# JACK_DUAL_M2_v3.net
KiCad netlist of a schematic drawn in EAGLE
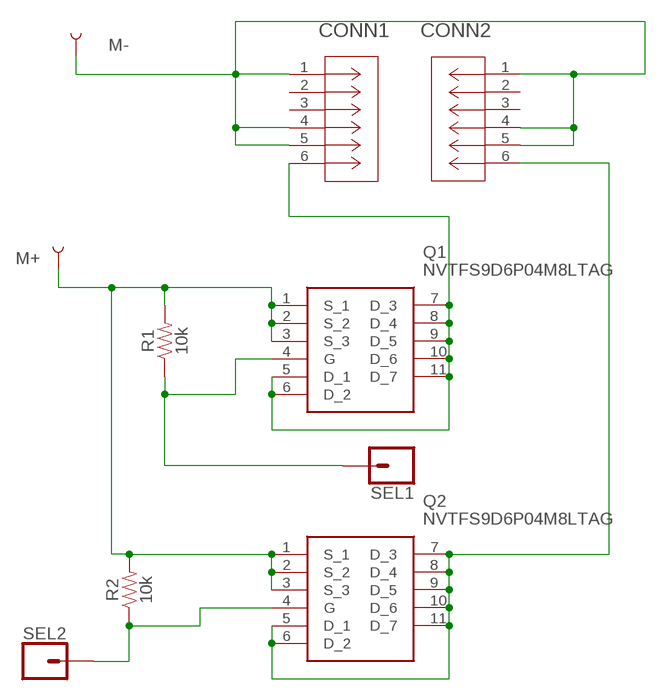
[diagram p0: schematic, sheet 1]

(export (version "E")
  (design (tool "Eeschema 10.0.6"))
  (components
    (comp (ref "CONN1")
      (value "ACJS-MHDR")
      (footprint "eagle-import:CONN_MHDR_AMP")
      (fields (field (name "COPYRIGHT") "Copyright (C) 2018 Accelerated Designs. All rights reserved"))
      (libsource (lib "eagle-import") (part "ACJS-MHDR"))
    )
    (comp (ref "CONN2")
      (value "ACJS-MHDR")
      (footprint "eagle-import:CONN_MHDR_AMP")
      (fields (field (name "COPYRIGHT") "Copyright (C) 2018 Accelerated Designs. All rights reserved"))
      (libsource (lib "eagle-import") (part "ACJS-MHDR"))
    )
    (comp (ref "M+")
      (value "TEST-POINT3")
      (footprint "eagle-import:PAD.03X.03")
      (libsource (lib "eagle-import") (part "TEST-POINT3"))
    )
    (comp (ref "M-")
      (value "TEST-POINT3")
      (footprint "eagle-import:PAD.03X.03")
      (libsource (lib "eagle-import") (part "TEST-POINT3"))
    )
    (comp (ref "Q1")
      (value "NVTFS9D6P04M8LTAG")
      (footprint "eagle-import:NVTFS5124PLTWG")
      (fields (field (name "MOUSER_PART_NUMBER") "863-NVTFS9D6P04M8LTG"))
      (libsource (lib "eagle-import") (part "NVTFS9D6P04M8LTAG"))
    )
    (comp (ref "Q2")
      (value "NVTFS9D6P04M8LTAG")
      (footprint "eagle-import:NVTFS5124PLTWG")
      (fields (field (name "MOUSER_PART_NUMBER") "863-NVTFS9D6P04M8LTG"))
      (libsource (lib "eagle-import") (part "NVTFS9D6P04M8LTAG"))
    )
    (comp (ref "R1")
      (value "10k")
      (footprint "eagle-import:0805")
      (libsource (lib "eagle-import") (part "RESISTOR0805"))
    )
    (comp (ref "R2")
      (value "10k")
      (footprint "eagle-import:0805")
      (libsource (lib "eagle-import") (part "RESISTOR0805"))
    )
    (comp (ref "SEL1")
      (value "CONN_01")
      (footprint "eagle-import:1X01")
      (libsource (lib "eagle-import") (part "CONN_01"))
    )
    (comp (ref "SEL2")
      (value "CONN_01")
      (footprint "eagle-import:1X01")
      (libsource (lib "eagle-import") (part "CONN_01"))
    )
  )
  (nets
    (net (code "1") (name "Net-(M+-1)") (class "Default")
      (node (ref "M+") (pin "P$1") (pinfunction "1_P$1") (pintype "bidirectional"))
      (node (ref "Q1") (pin "1") (pinfunction "S_1_1") (pintype "bidirectional"))
      (node (ref "Q1") (pin "2") (pinfunction "S_2_2") (pintype "bidirectional"))
      (node (ref "Q1") (pin "3") (pinfunction "S_3_3") (pintype "bidirectional"))
      (node (ref "Q2") (pin "1") (pinfunction "S_1_1") (pintype "bidirectional"))
      (node (ref "Q2") (pin "2") (pinfunction "S_2_2") (pintype "bidirectional"))
      (node (ref "Q2") (pin "3") (pinfunction "S_3_3") (pintype "bidirectional"))
      (node (ref "R1") (pin "2") (pinfunction "2_2") (pintype "passive"))
      (node (ref "R2") (pin "2") (pinfunction "2_2") (pintype "passive"))
    )
    (net (code "2") (name "Net-(M--1)") (class "Default")
      (node (ref "CONN1") (pin "1") (pinfunction "1_1") (pintype "passive"))
      (node (ref "CONN1") (pin "4") (pinfunction "4_4") (pintype "passive"))
      (node (ref "CONN1") (pin "5") (pinfunction "5_5") (pintype "passive"))
      (node (ref "CONN2") (pin "1") (pinfunction "1_1") (pintype "passive"))
      (node (ref "CONN2") (pin "4") (pinfunction "4_4") (pintype "passive"))
      (node (ref "CONN2") (pin "5") (pinfunction "5_5") (pintype "passive"))
      (node (ref "M-") (pin "P$1") (pinfunction "1_P$1") (pintype "bidirectional"))
    )
    (net (code "3") (name "Net-(Q1-D_1)") (class "Default")
      (node (ref "CONN1") (pin "6") (pinfunction "6_6") (pintype "passive"))
      (node (ref "Q1") (pin "10") (pinfunction "D_6_10") (pintype "bidirectional"))
      (node (ref "Q1") (pin "11") (pinfunction "D_7_11") (pintype "bidirectional"))
      (node (ref "Q1") (pin "5") (pinfunction "D_1_5") (pintype "bidirectional"))
      (node (ref "Q1") (pin "6") (pinfunction "D_2_6") (pintype "bidirectional"))
      (node (ref "Q1") (pin "7") (pinfunction "D_3_7") (pintype "bidirectional"))
      (node (ref "Q1") (pin "8") (pinfunction "D_4_8") (pintype "bidirectional"))
      (node (ref "Q1") (pin "9") (pinfunction "D_5_9") (pintype "bidirectional"))
    )
    (net (code "4") (name "Net-(Q1-G)") (class "Default")
      (node (ref "Q1") (pin "4") (pinfunction "G_4") (pintype "bidirectional"))
      (node (ref "R1") (pin "1") (pinfunction "1_1") (pintype "passive"))
      (node (ref "SEL1") (pin "1") (pinfunction "1_1") (pintype "passive"))
    )
    (net (code "5") (name "Net-(Q2-D_1)") (class "Default")
      (node (ref "CONN2") (pin "6") (pinfunction "6_6") (pintype "passive"))
      (node (ref "Q2") (pin "10") (pinfunction "D_6_10") (pintype "bidirectional"))
      (node (ref "Q2") (pin "11") (pinfunction "D_7_11") (pintype "bidirectional"))
      (node (ref "Q2") (pin "5") (pinfunction "D_1_5") (pintype "bidirectional"))
      (node (ref "Q2") (pin "6") (pinfunction "D_2_6") (pintype "bidirectional"))
      (node (ref "Q2") (pin "7") (pinfunction "D_3_7") (pintype "bidirectional"))
      (node (ref "Q2") (pin "8") (pinfunction "D_4_8") (pintype "bidirectional"))
      (node (ref "Q2") (pin "9") (pinfunction "D_5_9") (pintype "bidirectional"))
    )
    (net (code "6") (name "Net-(Q2-G)") (class "Default")
      (node (ref "Q2") (pin "4") (pinfunction "G_4") (pintype "bidirectional"))
      (node (ref "R2") (pin "1") (pinfunction "1_1") (pintype "passive"))
      (node (ref "SEL2") (pin "1") (pinfunction "1_1") (pintype "passive"))
    )
    (net (code "7") (name "unconnected-(CONN1-Pad2)") (class "Default")
      (node (ref "CONN1") (pin "2") (pinfunction "2_2") (pintype "passive"))
    )
    (net (code "8") (name "unconnected-(CONN1-Pad3)") (class "Default")
      (node (ref "CONN1") (pin "3") (pinfunction "3_3") (pintype "passive"))
    )
    (net (code "9") (name "unconnected-(CONN2-Pad2)") (class "Default")
      (node (ref "CONN2") (pin "2") (pinfunction "2_2") (pintype "passive"))
    )
    (net (code "10") (name "unconnected-(CONN2-Pad3)") (class "Default")
      (node (ref "CONN2") (pin "3") (pinfunction "3_3") (pintype "passive"))
    )
  )
)
